# H01R0_Frontend.net
KiCad netlist of a schematic drawn in Altium Designer
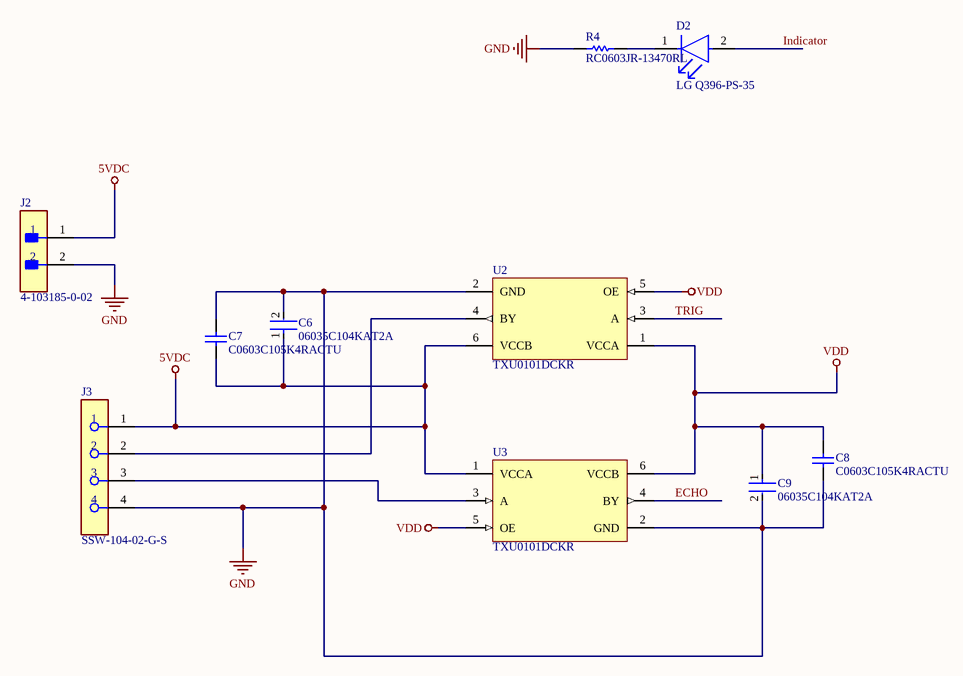
[diagram p0: H01R0_Frontend.SchDoc]

(export (version "E")
  (design (tool "Eeschema 10.0.6"))
  (components
    (comp (ref "C6")
      (value "06035C104KAT2A")
      (footprint "FP-0603-L_1_6_0_15-W_0_81-MFG")
      (description "General Purpose Ceramic Capacitor, 0603, 100nF, 10%, X7R, 15%, 50V")
      (fields (field (name "TOLERANCE") "10%") (field (name "VOLTAGE") "50V"))
      (libsource (lib "Altium Content Vault") (part "02cd4be3c70576c341d710602a673aa"))
    )
    (comp (ref "C7")
      (value "C0603C105K4RACTU")
      (footprint "CAPC1608X90X35LL15T15")
      (description "Ceramic capacitor, 1 µF, 16 V (DC), ±10 %, SMD 0603, X7R, C0603C105K4RAC7867")
      (fields (field (name "MANUFACTURER") "Kemet") (field (name "TOLERANCE") "10%"))
      (libsource (lib "Altium Content Vault") (part "CAP"))
    )
    (comp (ref "C8")
      (value "C0603C105K4RACTU")
      (footprint "CAPC1608X90X35LL15T15")
      (description "Ceramic capacitor, 1 µF, 16 V (DC), ±10 %, SMD 0603, X7R, C0603C105K4RAC7867")
      (fields (field (name "MANUFACTURER") "Kemet") (field (name "TOLERANCE") "10%"))
      (libsource (lib "Altium Content Vault") (part "CAP"))
    )
    (comp (ref "C9")
      (value "06035C104KAT2A")
      (footprint "FP-0603-L_1_6_0_15-W_0_81-MFG")
      (description "General Purpose Ceramic Capacitor, 0603, 100nF, 10%, X7R, 15%, 50V")
      (fields (field (name "TOLERANCE") "10%") (field (name "VOLTAGE") "50V"))
      (libsource (lib "Altium Content Vault") (part "02cd4be3c70576c341d710602a673aa"))
    )
    (comp (ref "D2")
      (value "LG Q396-PS-35")
      (footprint "FP-LG_Q396-MFG")
      (description "LED Uni-Color Green 2-Pin Chip 0603(1608Metric) T/R")
      (fields (field (name "MANUFACTURER") "Osram"))
      (libsource (lib "Altium Content Vault") (part "8706943c75ba83719d021d2fdc84c58"))
    )
    (comp (ref "J2")
      (value "4-103185-0-02")
      (footprint "FP-4-103185-0-02-MFG")
      (description "Conn Header Vert 2POS 2.54MM")
      (fields (field (name "MANUFACTURER") "TE Connectivity / AMP"))
      (libsource (lib "Altium Content Vault") (part "3bc925449376181038e59eaffc5286c"))
    )
    (comp (ref "J3")
      (value "SSW-104-02-G-S")
      (footprint "FP-SSW-104-02-G-S-MFG")
      (description "PCB Receptacle, Board-to-Board, 2.54 mm, 1 Rows, 4 Contacts, Through Hole Mount, SSW Series")
      (fields (field (name "MANUFACTURER") "Samtec"))
      (libsource (lib "Altium Content Vault") (part "56792406a6bd5c25e158f553ecd1aa7"))
    )
    (comp (ref "R4")
      (value "RC0603JR-13470RL")
      (footprint "RESC1608X55X25LL10T15")
      (description "Res Thick Film 0603 470 Ohm 5% 0.1W(1/10W) ±100ppm/C Pad SMD T/R")
      (fields (field (name "MANUFACTURER") "Yageo") (field (name "TOLERANCE") "5%"))
      (libsource (lib "Altium Content Vault") (part "RES"))
    )
    (comp (ref "U2")
      (value "TXU0101DCKR")
      (footprint "FP-DCK0006A-MFG")
      (description "Single channel fixed-direction level shifter 6-SC70 -40 to 125")
      (fields (field (name "MANUFACTURER") "Texas Instruments"))
      (libsource (lib "") (part "TXU0101DCKR_1"))
    )
    (comp (ref "U3")
      (value "TXU0101DCKR")
      (footprint "FP-DCK0006A-MFG")
      (description "Single channel fixed-direction level shifter 6-SC70 -40 to 125")
      (fields (field (name "MANUFACTURER") "Texas Instruments"))
      (libsource (lib "Altium Content Vault") (part "TXU0101DCKR"))
    )
  )
  (nets
    (net (code "1") (name "/ECHO") (class "Default")
      (node (ref "U3") (pin "4") (pinfunction "BY_4") (pintype "output"))
    )
    (net (code "2") (name "/Indicator") (class "Default")
      (node (ref "D2") (pin "2") (pinfunction "A_2") (pintype "passive"))
    )
    (net (code "3") (name "/TRIG") (class "Default")
      (node (ref "U2") (pin "3") (pinfunction "A_3") (pintype "input"))
    )
    (net (code "4") (name "5VDC") (class "Default")
      (node (ref "C6") (pin "1") (pinfunction "1_1") (pintype "passive"))
      (node (ref "C7") (pin "1") (pinfunction "1_1") (pintype "passive"))
      (node (ref "J2") (pin "1") (pinfunction "1_1") (pintype "passive"))
      (node (ref "J3") (pin "1") (pinfunction "1_1") (pintype "passive"))
      (node (ref "U2") (pin "6") (pinfunction "VCCB_6") (pintype "power_in"))
      (node (ref "U3") (pin "1") (pinfunction "VCCA_1") (pintype "power_in"))
    )
    (net (code "5") (name "GND") (class "Default")
      (node (ref "C6") (pin "2") (pinfunction "2_2") (pintype "passive"))
      (node (ref "C7") (pin "2") (pinfunction "2_2") (pintype "passive"))
      (node (ref "C8") (pin "2") (pinfunction "2_2") (pintype "passive"))
      (node (ref "C9") (pin "2") (pinfunction "2_2") (pintype "passive"))
      (node (ref "J2") (pin "2") (pinfunction "2_2") (pintype "passive"))
      (node (ref "J3") (pin "4") (pinfunction "4_4") (pintype "passive"))
      (node (ref "R4") (pin "1") (pinfunction "1_1") (pintype "passive"))
      (node (ref "U2") (pin "2") (pinfunction "GND_2") (pintype "power_in"))
      (node (ref "U3") (pin "2") (pinfunction "GND_2") (pintype "power_in"))
    )
    (net (code "6") (name "Net-(D2-C)") (class "Default")
      (node (ref "D2") (pin "1") (pinfunction "C_1") (pintype "passive"))
      (node (ref "R4") (pin "2") (pinfunction "2_2") (pintype "passive"))
    )
    (net (code "7") (name "Net-(U2-BY)") (class "Default")
      (node (ref "J3") (pin "2") (pinfunction "2_2") (pintype "passive"))
      (node (ref "U2") (pin "4") (pinfunction "BY_4") (pintype "output"))
    )
    (net (code "8") (name "Net-(U3-A)") (class "Default")
      (node (ref "J3") (pin "3") (pinfunction "3_3") (pintype "passive"))
      (node (ref "U3") (pin "3") (pinfunction "A_3") (pintype "input"))
    )
    (net (code "9") (name "VDD") (class "Default")
      (node (ref "C8") (pin "1") (pinfunction "1_1") (pintype "passive"))
      (node (ref "C9") (pin "1") (pinfunction "1_1") (pintype "passive"))
      (node (ref "U2") (pin "1") (pinfunction "VCCA_1") (pintype "power_in"))
      (node (ref "U2") (pin "5") (pinfunction "OE_5") (pintype "input"))
      (node (ref "U3") (pin "5") (pinfunction "OE_5") (pintype "input"))
      (node (ref "U3") (pin "6") (pinfunction "VCCB_6") (pintype "power_in"))
    )
  )
)
